# MainSchematic.net
KiCad netlist of a schematic drawn in Altium Designer
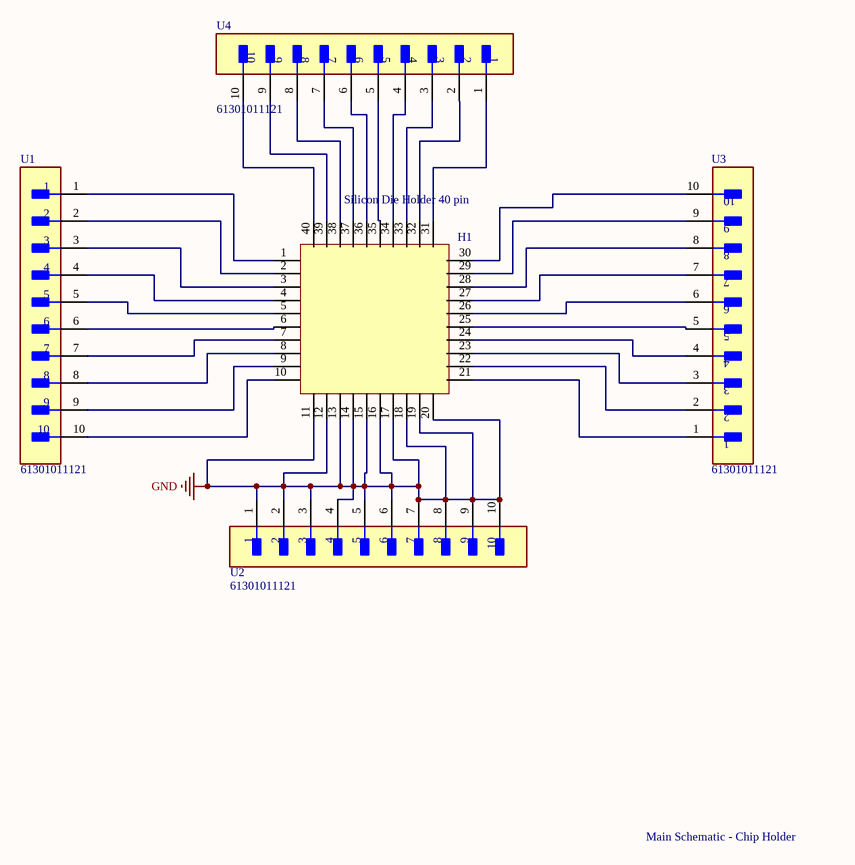
[diagram p0: MainSchematic.SchDoc]

(export (version "E")
  (design (tool "Eeschema 10.0.6"))
  (components
    (comp (ref "H1")
      (value "Silicon Die Holder 40 pin")
      (footprint "CQFP200P2508X2508X310-40N")
      (description "Silicon die holder 40 pin 20mm")
      (fields (field (name "PART NUMBER") "Silicon Die Holder 40 pin 20mm"))
      (libsource (lib "Celestial Library Database") (part "Silicon Die Holder 40 pin"))
    )
    (comp (ref "U1")
      (value "61301011121")
      (footprint "FP-61301011121-MFG")
      (description "CONN HEADER VERT 10POS 2.54MM")
      (libsource (lib "") (part "aee40dc8b284c03a16094555aa210be_3"))
    )
    (comp (ref "U2")
      (value "61301011121")
      (footprint "FP-61301011121-MFG")
      (description "CONN HEADER VERT 10POS 2.54MM")
      (libsource (lib "") (part "aee40dc8b284c03a16094555aa210be_2"))
    )
    (comp (ref "U3")
      (value "61301011121")
      (footprint "FP-61301011121-MFG")
      (description "CONN HEADER VERT 10POS 2.54MM")
      (libsource (lib "Altium Content Vault") (part "aee40dc8b284c03a16094555aa210be"))
    )
    (comp (ref "U4")
      (value "61301011121")
      (footprint "FP-61301011121-MFG")
      (description "CONN HEADER VERT 10POS 2.54MM")
      (libsource (lib "") (part "aee40dc8b284c03a16094555aa210be_1"))
    )
  )
  (nets
    (net (code "1") (name "GND") (class "Default")
      (node (ref "H1") (pin "11") (pintype "passive"))
      (node (ref "H1") (pin "12") (pintype "passive"))
      (node (ref "H1") (pin "13") (pintype "passive"))
      (node (ref "H1") (pin "14") (pintype "passive"))
      (node (ref "H1") (pin "15") (pintype "passive"))
      (node (ref "H1") (pin "16") (pintype "passive"))
      (node (ref "H1") (pin "17") (pintype "passive"))
      (node (ref "H1") (pin "18") (pintype "passive"))
      (node (ref "H1") (pin "19") (pintype "passive"))
      (node (ref "H1") (pin "20") (pintype "passive"))
      (node (ref "U2") (pin "1") (pinfunction "1_1") (pintype "passive"))
      (node (ref "U2") (pin "10") (pinfunction "10_10") (pintype "passive"))
      (node (ref "U2") (pin "2") (pinfunction "2_2") (pintype "passive"))
      (node (ref "U2") (pin "3") (pinfunction "3_3") (pintype "passive"))
      (node (ref "U2") (pin "4") (pinfunction "4_4") (pintype "passive"))
      (node (ref "U2") (pin "5") (pinfunction "5_5") (pintype "passive"))
      (node (ref "U2") (pin "6") (pinfunction "6_6") (pintype "passive"))
      (node (ref "U2") (pin "7") (pinfunction "7_7") (pintype "passive"))
      (node (ref "U2") (pin "8") (pinfunction "8_8") (pintype "passive"))
      (node (ref "U2") (pin "9") (pinfunction "9_9") (pintype "passive"))
    )
    (net (code "2") (name "Net-(H1-Pad1)") (class "Default")
      (node (ref "H1") (pin "1") (pintype "passive"))
      (node (ref "U1") (pin "1") (pinfunction "1_1") (pintype "passive"))
    )
    (net (code "3") (name "Net-(H1-Pad2)") (class "Default")
      (node (ref "H1") (pin "2") (pintype "passive"))
      (node (ref "U1") (pin "2") (pinfunction "2_2") (pintype "passive"))
    )
    (net (code "4") (name "Net-(H1-Pad3)") (class "Default")
      (node (ref "H1") (pin "3") (pintype "passive"))
      (node (ref "U1") (pin "3") (pinfunction "3_3") (pintype "passive"))
    )
    (net (code "5") (name "Net-(H1-Pad4)") (class "Default")
      (node (ref "H1") (pin "4") (pintype "passive"))
      (node (ref "U1") (pin "4") (pinfunction "4_4") (pintype "passive"))
    )
    (net (code "6") (name "Net-(H1-Pad5)") (class "Default")
      (node (ref "H1") (pin "5") (pintype "passive"))
      (node (ref "U1") (pin "5") (pinfunction "5_5") (pintype "passive"))
    )
    (net (code "7") (name "Net-(H1-Pad6)") (class "Default")
      (node (ref "H1") (pin "6") (pintype "passive"))
      (node (ref "U1") (pin "6") (pinfunction "6_6") (pintype "passive"))
    )
    (net (code "8") (name "Net-(H1-Pad7)") (class "Default")
      (node (ref "H1") (pin "7") (pintype "passive"))
      (node (ref "U1") (pin "7") (pinfunction "7_7") (pintype "passive"))
    )
    (net (code "9") (name "Net-(H1-Pad8)") (class "Default")
      (node (ref "H1") (pin "8") (pintype "passive"))
      (node (ref "U1") (pin "8") (pinfunction "8_8") (pintype "passive"))
    )
    (net (code "10") (name "Net-(H1-Pad9)") (class "Default")
      (node (ref "H1") (pin "9") (pintype "passive"))
      (node (ref "U1") (pin "9") (pinfunction "9_9") (pintype "passive"))
    )
    (net (code "11") (name "Net-(H1-Pad10)") (class "Default")
      (node (ref "H1") (pin "10") (pintype "passive"))
      (node (ref "U1") (pin "10") (pinfunction "10_10") (pintype "passive"))
    )
    (net (code "12") (name "Net-(H1-Pad21)") (class "Default")
      (node (ref "H1") (pin "21") (pintype "passive"))
      (node (ref "U3") (pin "1") (pinfunction "1_1") (pintype "passive"))
    )
    (net (code "13") (name "Net-(H1-Pad22)") (class "Default")
      (node (ref "H1") (pin "22") (pintype "passive"))
      (node (ref "U3") (pin "2") (pinfunction "2_2") (pintype "passive"))
    )
    (net (code "14") (name "Net-(H1-Pad23)") (class "Default")
      (node (ref "H1") (pin "23") (pintype "passive"))
      (node (ref "U3") (pin "3") (pinfunction "3_3") (pintype "passive"))
    )
    (net (code "15") (name "Net-(H1-Pad24)") (class "Default")
      (node (ref "H1") (pin "24") (pintype "passive"))
      (node (ref "U3") (pin "4") (pinfunction "4_4") (pintype "passive"))
    )
    (net (code "16") (name "Net-(H1-Pad25)") (class "Default")
      (node (ref "H1") (pin "25") (pintype "passive"))
      (node (ref "U3") (pin "5") (pinfunction "5_5") (pintype "passive"))
    )
    (net (code "17") (name "Net-(H1-Pad26)") (class "Default")
      (node (ref "H1") (pin "26") (pintype "passive"))
      (node (ref "U3") (pin "6") (pinfunction "6_6") (pintype "passive"))
    )
    (net (code "18") (name "Net-(H1-Pad27)") (class "Default")
      (node (ref "H1") (pin "27") (pintype "passive"))
      (node (ref "U3") (pin "7") (pinfunction "7_7") (pintype "passive"))
    )
    (net (code "19") (name "Net-(H1-Pad28)") (class "Default")
      (node (ref "H1") (pin "28") (pintype "passive"))
      (node (ref "U3") (pin "8") (pinfunction "8_8") (pintype "passive"))
    )
    (net (code "20") (name "Net-(H1-Pad29)") (class "Default")
      (node (ref "H1") (pin "29") (pintype "passive"))
      (node (ref "U3") (pin "9") (pinfunction "9_9") (pintype "passive"))
    )
    (net (code "21") (name "Net-(H1-Pad30)") (class "Default")
      (node (ref "H1") (pin "30") (pintype "passive"))
      (node (ref "U3") (pin "10") (pinfunction "10_10") (pintype "passive"))
    )
    (net (code "22") (name "Net-(H1-Pad31)") (class "Default")
      (node (ref "H1") (pin "31") (pintype "passive"))
      (node (ref "U4") (pin "1") (pinfunction "1_1") (pintype "passive"))
    )
    (net (code "23") (name "Net-(H1-Pad32)") (class "Default")
      (node (ref "H1") (pin "32") (pintype "passive"))
      (node (ref "U4") (pin "2") (pinfunction "2_2") (pintype "passive"))
    )
    (net (code "24") (name "Net-(H1-Pad33)") (class "Default")
      (node (ref "H1") (pin "33") (pintype "passive"))
      (node (ref "U4") (pin "3") (pinfunction "3_3") (pintype "passive"))
    )
    (net (code "25") (name "Net-(H1-Pad34)") (class "Default")
      (node (ref "H1") (pin "34") (pintype "passive"))
      (node (ref "U4") (pin "4") (pinfunction "4_4") (pintype "passive"))
    )
    (net (code "26") (name "Net-(H1-Pad35)") (class "Default")
      (node (ref "H1") (pin "35") (pintype "passive"))
      (node (ref "U4") (pin "5") (pinfunction "5_5") (pintype "passive"))
    )
    (net (code "27") (name "Net-(H1-Pad36)") (class "Default")
      (node (ref "H1") (pin "36") (pintype "passive"))
      (node (ref "U4") (pin "6") (pinfunction "6_6") (pintype "passive"))
    )
    (net (code "28") (name "Net-(H1-Pad37)") (class "Default")
      (node (ref "H1") (pin "37") (pintype "passive"))
      (node (ref "U4") (pin "7") (pinfunction "7_7") (pintype "passive"))
    )
    (net (code "29") (name "Net-(H1-Pad38)") (class "Default")
      (node (ref "H1") (pin "38") (pintype "passive"))
      (node (ref "U4") (pin "8") (pinfunction "8_8") (pintype "passive"))
    )
    (net (code "30") (name "Net-(H1-Pad39)") (class "Default")
      (node (ref "H1") (pin "39") (pintype "passive"))
      (node (ref "U4") (pin "9") (pinfunction "9_9") (pintype "passive"))
    )
    (net (code "31") (name "Net-(H1-Pad40)") (class "Default")
      (node (ref "H1") (pin "40") (pintype "passive"))
      (node (ref "U4") (pin "10") (pinfunction "10_10") (pintype "passive"))
    )
  )
)
